# bpod_stepper_1_4_6.net
KiCad netlist of a schematic drawn in EAGLE
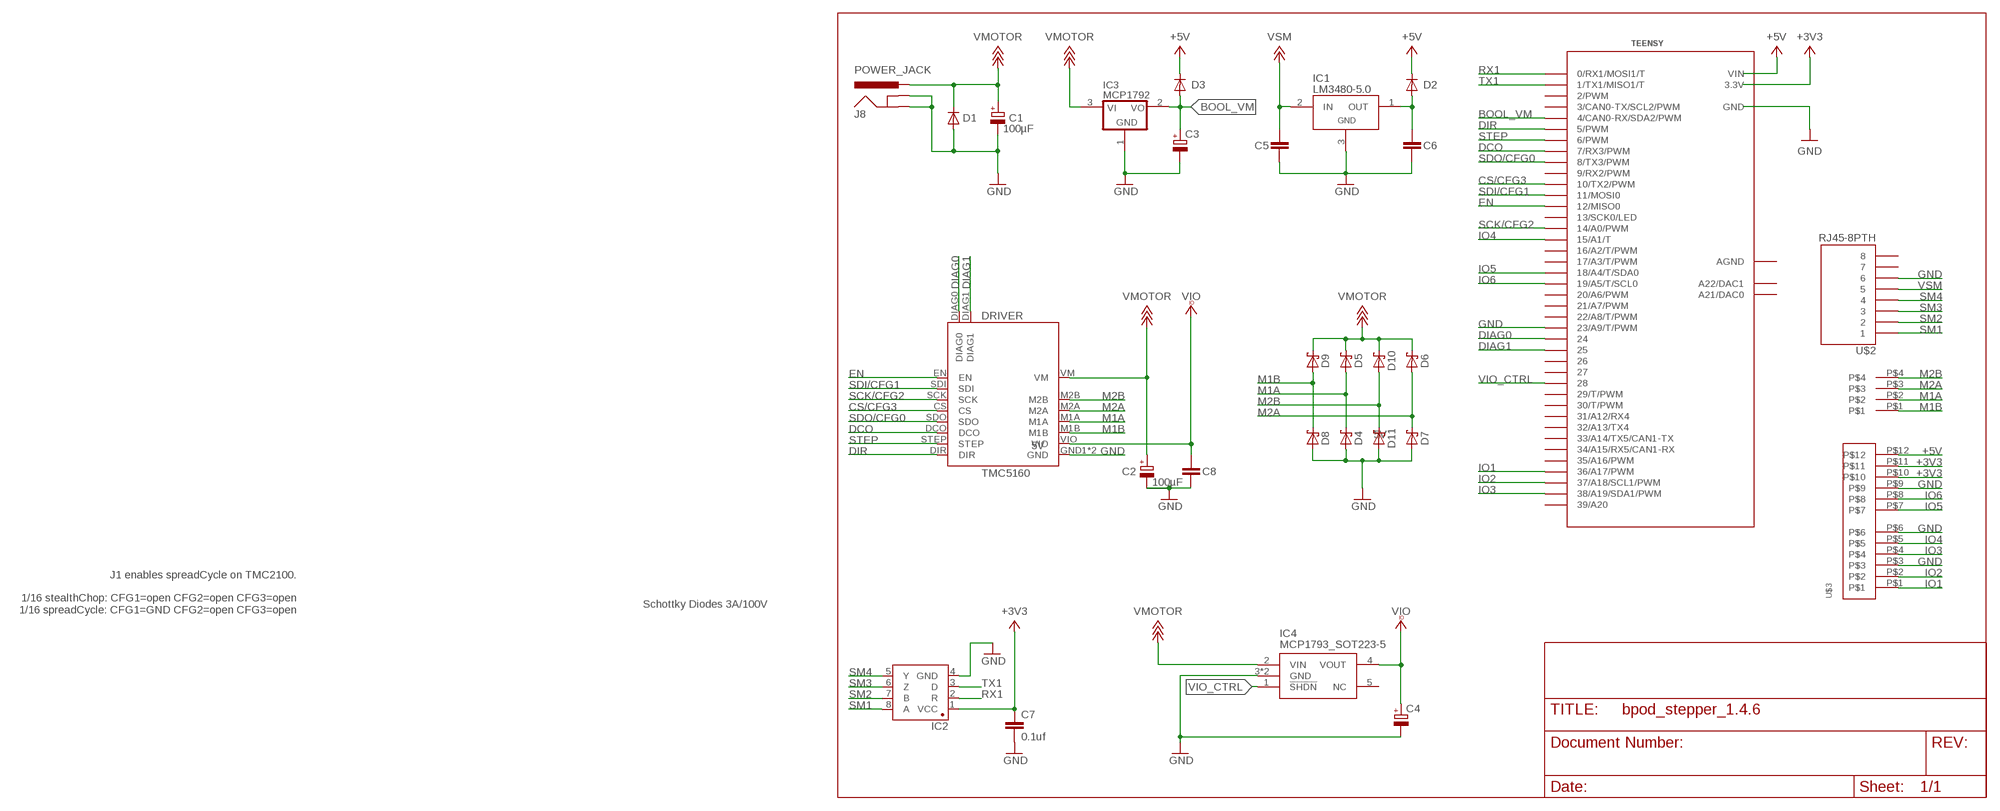
[diagram p0: schematic, sheet 1]

(export (version "E")
  (design (tool "Eeschema 10.0.6"))
  (components
    (comp (ref "C1")
      (value "100µF")
      (footprint "eagle-import:PANASONIC_G")
      (libsource (lib "eagle-import") (part "CPOL-EUG"))
    )
    (comp (ref "C2")
      (value "100µF")
      (footprint "eagle-import:PANASONIC_G")
      (libsource (lib "eagle-import") (part "CPOL-EUG"))
    )
    (comp (ref "C3")
      (value "CPOL-EUB")
      (footprint "eagle-import:PANASONIC_B")
      (libsource (lib "eagle-import") (part "CPOL-EUB"))
    )
    (comp (ref "C4")
      (value "CPOL-EUB")
      (footprint "eagle-import:PANASONIC_B")
      (libsource (lib "eagle-import") (part "CPOL-EUB"))
    )
    (comp (ref "C5")
      (value "0.1uf")
      (footprint "eagle-import:1206@1")
      (libsource (lib "eagle-import") (part "CAP1206"))
    )
    (comp (ref "C6")
      (value "0.1uf")
      (footprint "eagle-import:1206@1")
      (libsource (lib "eagle-import") (part "CAP1206"))
    )
    (comp (ref "C7")
      (value "0.1uf")
      (footprint "eagle-import:1206@1")
      (libsource (lib "eagle-import") (part "CAP1206"))
    )
    (comp (ref "C8")
      (value "100nf")
      (footprint "eagle-import:1206@1")
      (libsource (lib "eagle-import") (part "CAP1206"))
    )
    (comp (ref "D1")
      (value "DIODE-DO214AA")
      (footprint "eagle-import:DO214AA")
      (libsource (lib "eagle-import") (part "DIODE-DO214AA"))
    )
    (comp (ref "D2")
      (value "MBR0520LT")
      (footprint "eagle-import:SOD123")
      (libsource (lib "eagle-import") (part "MBR0520LT"))
    )
    (comp (ref "D3")
      (value "MBR0520LT")
      (footprint "eagle-import:SOD123")
      (libsource (lib "eagle-import") (part "MBR0520LT"))
    )
    (comp (ref "D4")
      (value "S310FA")
      (footprint "eagle-import:SOD123")
      (libsource (lib "eagle-import") (part "D_SCHOTTKY-SOD123"))
    )
    (comp (ref "D5")
      (value "S310FA")
      (footprint "eagle-import:SOD123")
      (libsource (lib "eagle-import") (part "D_SCHOTTKY-SOD123"))
    )
    (comp (ref "D6")
      (value "S310FA")
      (footprint "eagle-import:SOD123")
      (libsource (lib "eagle-import") (part "D_SCHOTTKY-SOD123"))
    )
    (comp (ref "D7")
      (value "S310FA")
      (footprint "eagle-import:SOD123")
      (libsource (lib "eagle-import") (part "D_SCHOTTKY-SOD123"))
    )
    (comp (ref "D8")
      (value "S310FA")
      (footprint "eagle-import:SOD123")
      (libsource (lib "eagle-import") (part "D_SCHOTTKY-SOD123"))
    )
    (comp (ref "D9")
      (value "S310FA")
      (footprint "eagle-import:SOD123")
      (libsource (lib "eagle-import") (part "D_SCHOTTKY-SOD123"))
    )
    (comp (ref "D10")
      (value "S310FA")
      (footprint "eagle-import:SOD123")
      (libsource (lib "eagle-import") (part "D_SCHOTTKY-SOD123"))
    )
    (comp (ref "D11")
      (value "S310FA")
      (footprint "eagle-import:SOD123")
      (libsource (lib "eagle-import") (part "D_SCHOTTKY-SOD123"))
    )
    (comp (ref "DRIVER")
      (value "TMC5160")
      (footprint "eagle-import:TMC5160")
      (libsource (lib "eagle-import") (part "TMC5160"))
    )
    (comp (ref "IC1")
      (value "LM3480-5.0")
      (footprint "eagle-import:SOT-23-3")
      (libsource (lib "eagle-import") (part "LM3480-5.0"))
    )
    (comp (ref "IC2")
      (value "SN65HVD31DR")
      (footprint "eagle-import:SO08")
      (libsource (lib "eagle-import") (part "SN65HVD31DR"))
    )
    (comp (ref "IC3")
      (value "MCP1792")
      (footprint "eagle-import:SOT23A_MICROCHIP_CB")
      (libsource (lib "eagle-import") (part "MCP170302E/CB-12"))
    )
    (comp (ref "IC4")
      (value "MCP1793_SOT223-5")
      (footprint "eagle-import:SOT223-5")
      (libsource (lib "eagle-import") (part "MCP1793_SOT223-5"))
    )
    (comp (ref "J8")
      (value "POWER_JACK")
      (footprint "eagle-import:POWER_JACK_PTH")
      (libsource (lib "eagle-import") (part "POWER_JACK"))
    )
    (comp (ref "TEENSY")
      (value "TEENSY_3.6_DIL")
      (footprint "eagle-import:TEENSY_3.6_DIL")
      (libsource (lib "eagle-import") (part "TEENSY_3.6_DIL"))
    )
    (comp (ref "U$2")
      (value "RJ45-8PTH")
      (footprint "eagle-import:RJ45-8")
      (libsource (lib "eagle-import") (part "RJ45-8PTH"))
    )
    (comp (ref "U$3")
      (value "12POS_MOLEX_SOCKET")
      (footprint "eagle-import:12POS_MOLEX_SOCKET")
      (libsource (lib "eagle-import") (part "12POS_MOLEX_SOCKET"))
    )
    (comp (ref "U$4")
      (value "MOLEX395221004")
      (footprint "eagle-import:MOLEX395221004")
      (libsource (lib "eagle-import") (part "MOLEX395221004"))
    )
  )
  (nets
    (net (code "1") (name "+3V3") (class "Default")
      (node (ref "C7") (pin "1") (pinfunction "1_1") (pintype "passive"))
      (node (ref "IC2") (pin "1") (pinfunction "VCC_1") (pintype "bidirectional"))
      (node (ref "TEENSY") (pin "3.3V") (pinfunction "3.3V_3.3V") (pintype "power_in"))
      (node (ref "TEENSY") (pin "3.3V3") (pinfunction "3.3V_3.3V3") (pintype "power_in"))
      (node (ref "U$3") (pin "P$10") (pinfunction "P$10_P$10") (pintype "bidirectional"))
      (node (ref "U$3") (pin "P$11") (pinfunction "P$11_P$11") (pintype "bidirectional"))
    )
    (net (code "2") (name "+5V") (class "Default")
      (node (ref "D2") (pin "C") (pinfunction "C_C") (pintype "passive"))
      (node (ref "D3") (pin "C") (pinfunction "C_C") (pintype "passive"))
      (node (ref "TEENSY") (pin "VIN") (pinfunction "VIN_VIN") (pintype "power_in"))
      (node (ref "U$3") (pin "P$12") (pinfunction "P$12_P$12") (pintype "bidirectional"))
    )
    (net (code "3") (name "+12V") (class "Default")
      (node (ref "C5") (pin "2") (pinfunction "2_2") (pintype "passive"))
      (node (ref "IC1") (pin "2") (pinfunction "IN_2") (pintype "power_in"))
      (node (ref "U$2") (pin "5") (pinfunction "5_5") (pintype "bidirectional"))
    )
    (net (code "4") (name "+18V") (class "Default")
      (node (ref "C1") (pin "+") (pinfunction "+_+") (pintype "passive"))
      (node (ref "C2") (pin "+") (pinfunction "+_+") (pintype "passive"))
      (node (ref "D1") (pin "C") (pinfunction "C_C") (pintype "passive"))
      (node (ref "D10") (pin "C") (pinfunction "C_C") (pintype "passive"))
      (node (ref "D5") (pin "C") (pinfunction "C_C") (pintype "passive"))
      (node (ref "D6") (pin "C") (pinfunction "C_C") (pintype "passive"))
      (node (ref "D9") (pin "C") (pinfunction "C_C") (pintype "passive"))
      (node (ref "DRIVER") (pin "VM") (pinfunction "VM_VM") (pintype "power_in"))
      (node (ref "IC3") (pin "3") (pinfunction "VI_3") (pintype "power_in"))
      (node (ref "IC4") (pin "2") (pinfunction "VIN_2") (pintype "bidirectional"))
      (node (ref "J8") (pin "PWR") (pinfunction "PWR_PWR") (pintype "bidirectional"))
    )
    (net (code "5") (name "/AGND") (class "Default")
      (node (ref "TEENSY") (pin "AGND") (pinfunction "AGND_AGND") (pintype "power_in"))
    )
    (net (code "6") (name "/CS{slash}CFG3") (class "Default")
      (node (ref "DRIVER") (pin "CS") (pinfunction "CS_CS") (pintype "passive"))
      (node (ref "TEENSY") (pin "10") (pinfunction "10/TX2/PWM_10") (pintype "bidirectional"))
    )
    (net (code "7") (name "/DCO") (class "Default")
      (node (ref "DRIVER") (pin "DCO") (pinfunction "DCO_DCO") (pintype "passive"))
      (node (ref "TEENSY") (pin "7") (pinfunction "7/RX3/PWM_7") (pintype "bidirectional"))
    )
    (net (code "8") (name "/DIAG0") (class "Default")
      (node (ref "DRIVER") (pin "DIAG0") (pinfunction "DIAG0_DIAG0") (pintype "passive"))
      (node (ref "TEENSY") (pin "24") (pinfunction "24_24") (pintype "bidirectional"))
    )
    (net (code "9") (name "/DIAG1") (class "Default")
      (node (ref "DRIVER") (pin "DIAG1") (pinfunction "DIAG1_DIAG1") (pintype "passive"))
      (node (ref "TEENSY") (pin "25") (pinfunction "25_25") (pintype "bidirectional"))
    )
    (net (code "10") (name "/DIR") (class "Default")
      (node (ref "DRIVER") (pin "DIR") (pinfunction "DIR_DIR") (pintype "input"))
      (node (ref "TEENSY") (pin "5") (pinfunction "5/PWM_5") (pintype "bidirectional"))
    )
    (net (code "11") (name "/EN") (class "Default")
      (node (ref "DRIVER") (pin "EN") (pinfunction "EN_EN") (pintype "passive"))
      (node (ref "TEENSY") (pin "12") (pinfunction "12/MISO0_12") (pintype "bidirectional"))
    )
    (net (code "12") (name "/IO1") (class "Default")
      (node (ref "TEENSY") (pin "36/A17") (pinfunction "36/A17/PWM_36/A17") (pintype "bidirectional"))
      (node (ref "U$3") (pin "P$1") (pinfunction "P$1_P$1") (pintype "bidirectional"))
    )
    (net (code "13") (name "/IO2") (class "Default")
      (node (ref "TEENSY") (pin "37/A18") (pinfunction "37/A18/SCL1/PWM_37/A18") (pintype "bidirectional"))
      (node (ref "U$3") (pin "P$2") (pinfunction "P$2_P$2") (pintype "bidirectional"))
    )
    (net (code "14") (name "/IO3") (class "Default")
      (node (ref "TEENSY") (pin "38/A19") (pinfunction "38/A19/SDA1/PWM_38/A19") (pintype "bidirectional"))
      (node (ref "U$3") (pin "P$4") (pinfunction "P$4_P$4") (pintype "bidirectional"))
    )
    (net (code "15") (name "/IO4") (class "Default")
      (node (ref "TEENSY") (pin "15/A1") (pinfunction "15/A1/T_15/A1") (pintype "bidirectional"))
      (node (ref "U$3") (pin "P$5") (pinfunction "P$5_P$5") (pintype "bidirectional"))
    )
    (net (code "16") (name "/IO5") (class "Default")
      (node (ref "TEENSY") (pin "18/A4") (pinfunction "18/A4/T/SDA0_18/A4") (pintype "bidirectional"))
      (node (ref "U$3") (pin "P$7") (pinfunction "P$7_P$7") (pintype "bidirectional"))
    )
    (net (code "17") (name "/IO6") (class "Default")
      (node (ref "TEENSY") (pin "19/A5") (pinfunction "19/A5/T/SCL0_19/A5") (pintype "bidirectional"))
      (node (ref "U$3") (pin "P$8") (pinfunction "P$8_P$8") (pintype "bidirectional"))
    )
    (net (code "18") (name "/M1A") (class "Default")
      (node (ref "D4") (pin "C") (pinfunction "C_C") (pintype "passive"))
      (node (ref "D5") (pin "A") (pinfunction "A_A") (pintype "passive"))
      (node (ref "DRIVER") (pin "M1A") (pinfunction "M1A_M1A") (pintype "output"))
      (node (ref "U$4") (pin "P$2") (pinfunction "P$2_P$2") (pintype "bidirectional"))
    )
    (net (code "19") (name "/M1B") (class "Default")
      (node (ref "D8") (pin "C") (pinfunction "C_C") (pintype "passive"))
      (node (ref "D9") (pin "A") (pinfunction "A_A") (pintype "passive"))
      (node (ref "DRIVER") (pin "M1B") (pinfunction "M1B_M1B") (pintype "output"))
      (node (ref "U$4") (pin "P$1") (pinfunction "P$1_P$1") (pintype "bidirectional"))
    )
    (net (code "20") (name "/M2A") (class "Default")
      (node (ref "D6") (pin "A") (pinfunction "A_A") (pintype "passive"))
      (node (ref "D7") (pin "C") (pinfunction "C_C") (pintype "passive"))
      (node (ref "DRIVER") (pin "M2A") (pinfunction "M2A_M2A") (pintype "output"))
      (node (ref "U$4") (pin "P$3") (pinfunction "P$3_P$3") (pintype "bidirectional"))
    )
    (net (code "21") (name "/M2B") (class "Default")
      (node (ref "D10") (pin "A") (pinfunction "A_A") (pintype "passive"))
      (node (ref "D11") (pin "C") (pinfunction "C_C") (pintype "passive"))
      (node (ref "DRIVER") (pin "M2B") (pinfunction "M2B_M2B") (pintype "output"))
      (node (ref "U$4") (pin "P$4") (pinfunction "P$4_P$4") (pintype "bidirectional"))
    )
    (net (code "22") (name "/RX1") (class "Default")
      (node (ref "IC2") (pin "2") (pinfunction "R_2") (pintype "bidirectional"))
      (node (ref "TEENSY") (pin "0") (pinfunction "0/RX1/MOSI1/T_0") (pintype "bidirectional"))
    )
    (net (code "23") (name "/SCK{slash}CFG2") (class "Default")
      (node (ref "DRIVER") (pin "SCK") (pinfunction "SCK_SCK") (pintype "passive"))
      (node (ref "TEENSY") (pin "14/A0") (pinfunction "14/A0/PWM_14/A0") (pintype "bidirectional"))
    )
    (net (code "24") (name "/SDI{slash}CFG1") (class "Default")
      (node (ref "DRIVER") (pin "SDI") (pinfunction "SDI_SDI") (pintype "passive"))
      (node (ref "TEENSY") (pin "11") (pinfunction "11/MOSI0_11") (pintype "bidirectional"))
    )
    (net (code "25") (name "/SDO{slash}CFG0") (class "Default")
      (node (ref "DRIVER") (pin "SDO") (pinfunction "SDO_SDO") (pintype "passive"))
      (node (ref "TEENSY") (pin "8") (pinfunction "8/TX3/PWM_8") (pintype "bidirectional"))
    )
    (net (code "26") (name "/SM1") (class "Default")
      (node (ref "IC2") (pin "8") (pinfunction "A_8") (pintype "bidirectional"))
      (node (ref "U$2") (pin "1") (pinfunction "1_1") (pintype "bidirectional"))
    )
    (net (code "27") (name "/SM2") (class "Default")
      (node (ref "IC2") (pin "7") (pinfunction "B_7") (pintype "bidirectional"))
      (node (ref "U$2") (pin "2") (pinfunction "2_2") (pintype "bidirectional"))
    )
    (net (code "28") (name "/SM3") (class "Default")
      (node (ref "IC2") (pin "6") (pinfunction "Z_6") (pintype "bidirectional"))
      (node (ref "U$2") (pin "3") (pinfunction "3_3") (pintype "bidirectional"))
    )
    (net (code "29") (name "/SM4") (class "Default")
      (node (ref "IC2") (pin "5") (pinfunction "Y_5") (pintype "bidirectional"))
      (node (ref "U$2") (pin "4") (pinfunction "4_4") (pintype "bidirectional"))
    )
    (net (code "30") (name "/STEP") (class "Default")
      (node (ref "DRIVER") (pin "STEP") (pinfunction "STEP_STEP") (pintype "input"))
      (node (ref "TEENSY") (pin "6") (pinfunction "6/PWM_6") (pintype "bidirectional"))
    )
    (net (code "31") (name "/TX1") (class "Default")
      (node (ref "IC2") (pin "3") (pinfunction "D_3") (pintype "bidirectional"))
      (node (ref "TEENSY") (pin "1") (pinfunction "1/TX1/MISO1/T_1") (pintype "bidirectional"))
    )
    (net (code "32") (name "BOOL_VM") (class "Default")
      (node (ref "C3") (pin "+") (pinfunction "+_+") (pintype "passive"))
      (node (ref "D3") (pin "A") (pinfunction "A_A") (pintype "passive"))
      (node (ref "IC3") (pin "2") (pinfunction "VO_2") (pintype "passive"))
      (node (ref "TEENSY") (pin "4") (pinfunction "4/CAN0-RX/SDA2/PWM_4") (pintype "bidirectional"))
    )
    (net (code "33") (name "GND") (class "Default")
      (node (ref "C1") (pin "-") (pinfunction "-_-") (pintype "passive"))
      (node (ref "C2") (pin "-") (pinfunction "-_-") (pintype "passive"))
      (node (ref "C3") (pin "-") (pinfunction "-_-") (pintype "passive"))
      (node (ref "C4") (pin "-") (pinfunction "-_-") (pintype "passive"))
      (node (ref "C5") (pin "1") (pinfunction "1_1") (pintype "passive"))
      (node (ref "C6") (pin "1") (pinfunction "1_1") (pintype "passive"))
      (node (ref "C7") (pin "2") (pinfunction "2_2") (pintype "passive"))
      (node (ref "C8") (pin "2") (pinfunction "2_2") (pintype "passive"))
      (node (ref "D1") (pin "A") (pinfunction "A_A") (pintype "passive"))
      (node (ref "D11") (pin "A") (pinfunction "A_A") (pintype "passive"))
      (node (ref "D4") (pin "A") (pinfunction "A_A") (pintype "passive"))
      (node (ref "D7") (pin "A") (pinfunction "A_A") (pintype "passive"))
      (node (ref "D8") (pin "A") (pinfunction "A_A") (pintype "passive"))
      (node (ref "DRIVER") (pin "GND1") (pinfunction "GND_GND1") (pintype "power_in"))
      (node (ref "DRIVER") (pin "GND2") (pinfunction "GND_GND2") (pintype "power_in"))
      (node (ref "IC1") (pin "3") (pinfunction "GND_3") (pintype "power_in"))
      (node (ref "IC2") (pin "4") (pinfunction "GND_4") (pintype "bidirectional"))
      (node (ref "IC3") (pin "1") (pinfunction "GND_1") (pintype "power_in"))
      (node (ref "IC4") (pin "3") (pinfunction "GND_3") (pintype "bidirectional"))
      (node (ref "IC4") (pin "6") (pinfunction "GND_6") (pintype "bidirectional"))
      (node (ref "J8") (pin "GND") (pinfunction "GND_GND") (pintype "bidirectional"))
      (node (ref "J8") (pin "GNDBREAK") (pinfunction "GNDBREAK_GNDBREAK") (pintype "bidirectional"))
      (node (ref "TEENSY") (pin "23/A9") (pinfunction "23/A9/T/PWM_23/A9") (pintype "bidirectional"))
      (node (ref "TEENSY") (pin "GND") (pinfunction "GND_GND") (pintype "power_in"))
      (node (ref "TEENSY") (pin "GND1") (pinfunction "GND_GND1") (pintype "power_in"))
      (node (ref "U$2") (pin "6") (pinfunction "6_6") (pintype "bidirectional"))
      (node (ref "U$3") (pin "P$3") (pinfunction "P$3_P$3") (pintype "bidirectional"))
      (node (ref "U$3") (pin "P$6") (pinfunction "P$6_P$6") (pintype "bidirectional"))
      (node (ref "U$3") (pin "P$9") (pinfunction "P$9_P$9") (pintype "bidirectional"))
    )
    (net (code "34") (name "Net-(IC1-OUT)") (class "Default")
      (node (ref "C6") (pin "2") (pinfunction "2_2") (pintype "passive"))
      (node (ref "D2") (pin "A") (pinfunction "A_A") (pintype "passive"))
      (node (ref "IC1") (pin "1") (pinfunction "OUT_1") (pintype "power_in"))
    )
    (net (code "35") (name "VCCIO") (class "Default")
      (node (ref "C4") (pin "+") (pinfunction "+_+") (pintype "passive"))
      (node (ref "C8") (pin "1") (pinfunction "1_1") (pintype "passive"))
      (node (ref "DRIVER") (pin "VIO") (pinfunction "VIO_VIO") (pintype "power_in"))
      (node (ref "IC4") (pin "4") (pinfunction "VOUT_4") (pintype "bidirectional"))
    )
    (net (code "36") (name "VIO_CTRL") (class "Default")
      (node (ref "IC4") (pin "1") (pinfunction "~{SHDN}_1") (pintype "bidirectional"))
      (node (ref "TEENSY") (pin "28") (pinfunction "28_28") (pintype "bidirectional"))
    )
    (net (code "37") (name "unconnected-(IC4-NC-Pad5)") (class "Default")
      (node (ref "IC4") (pin "5") (pinfunction "NC_5") (pintype "bidirectional"))
    )
    (net (code "38") (name "unconnected-(TEENSY-2{slash}PWM-Pad2)") (class "Default")
      (node (ref "TEENSY") (pin "2") (pinfunction "2/PWM_2") (pintype "bidirectional"))
    )
    (net (code "39") (name "unconnected-(TEENSY-3{slash}CAN0-TX{slash}SCL2{slash}PWM-Pad3)") (class "Default")
      (node (ref "TEENSY") (pin "3") (pinfunction "3/CAN0-TX/SCL2/PWM_3") (pintype "bidirectional"))
    )
    (net (code "40") (name "unconnected-(TEENSY-9{slash}RX2{slash}PWM-Pad9)") (class "Default")
      (node (ref "TEENSY") (pin "9") (pinfunction "9/RX2/PWM_9") (pintype "bidirectional"))
    )
    (net (code "41") (name "unconnected-(TEENSY-13{slash}SCK0{slash}LED-Pad13)") (class "Default")
      (node (ref "TEENSY") (pin "13") (pinfunction "13/SCK0/LED_13") (pintype "bidirectional"))
    )
    (net (code "42") (name "unconnected-(TEENSY-16{slash}A2{slash}T{slash}PWM-Pad16{slash}A2)") (class "Default")
      (node (ref "TEENSY") (pin "16/A2") (pinfunction "16/A2/T/PWM_16/A2") (pintype "bidirectional"))
    )
    (net (code "43") (name "unconnected-(TEENSY-17{slash}A3{slash}T{slash}PWM-Pad17{slash}A3)") (class "Default")
      (node (ref "TEENSY") (pin "17/A3") (pinfunction "17/A3/T/PWM_17/A3") (pintype "bidirectional"))
    )
    (net (code "44") (name "unconnected-(TEENSY-20{slash}A6{slash}PWM-Pad20{slash}A6)") (class "Default")
      (node (ref "TEENSY") (pin "20/A6") (pinfunction "20/A6/PWM_20/A6") (pintype "bidirectional"))
    )
    (net (code "45") (name "unconnected-(TEENSY-21{slash}A7{slash}PWM-Pad21{slash}A7)") (class "Default")
      (node (ref "TEENSY") (pin "21/A7") (pinfunction "21/A7/PWM_21/A7") (pintype "bidirectional"))
    )
    (net (code "46") (name "unconnected-(TEENSY-22{slash}A8{slash}T{slash}PWM-Pad22{slash}A8)") (class "Default")
      (node (ref "TEENSY") (pin "22/A8") (pinfunction "22/A8/T/PWM_22/A8") (pintype "bidirectional"))
    )
    (net (code "47") (name "unconnected-(TEENSY-29{slash}T{slash}PWM-Pad29)") (class "Default")
      (node (ref "TEENSY") (pin "29") (pinfunction "29/T/PWM_29") (pintype "bidirectional"))
    )
    (net (code "48") (name "unconnected-(TEENSY-30{slash}T{slash}PWM-Pad30)") (class "Default")
      (node (ref "TEENSY") (pin "30") (pinfunction "30/T/PWM_30") (pintype "bidirectional"))
    )
    (net (code "49") (name "unconnected-(TEENSY-31{slash}A12{slash}RX4-Pad31{slash}A12)") (class "Default")
      (node (ref "TEENSY") (pin "31/A12") (pinfunction "31/A12/RX4_31/A12") (pintype "bidirectional"))
    )
    (net (code "50") (name "unconnected-(TEENSY-32{slash}A13{slash}TX4-Pad32{slash}A13)") (class "Default")
      (node (ref "TEENSY") (pin "32/A13") (pinfunction "32/A13/TX4_32/A13") (pintype "bidirectional"))
    )
    (net (code "51") (name "unconnected-(TEENSY-33{slash}A14{slash}TX5{slash}CAN1-TX-Pad33{slash}A14)") (class "Default")
      (node (ref "TEENSY") (pin "33/A14") (pinfunction "33/A14/TX5/CAN1-TX_33/A14") (pintype "bidirectional"))
    )
    (net (code "52") (name "unconnected-(TEENSY-34{slash}A15{slash}RX5{slash}CAN1-RX-Pad34{slash}A15)") (class "Default")
      (node (ref "TEENSY") (pin "34/A15") (pinfunction "34/A15/RX5/CAN1-RX_34/A15") (pintype "bidirectional"))
    )
    (net (code "53") (name "unconnected-(TEENSY-35{slash}A16{slash}PWM-Pad35{slash}A16)") (class "Default")
      (node (ref "TEENSY") (pin "35/A16") (pinfunction "35/A16/PWM_35/A16") (pintype "bidirectional"))
    )
    (net (code "54") (name "unconnected-(TEENSY-A21{slash}DAC0-PadA21)") (class "Default")
      (node (ref "TEENSY") (pin "A21") (pinfunction "A21/DAC0_A21") (pintype "bidirectional"))
    )
    (net (code "55") (name "unconnected-(TEENSY-A22{slash}DAC1-PadA22)") (class "Default")
      (node (ref "TEENSY") (pin "A22") (pinfunction "A22/DAC1_A22") (pintype "bidirectional"))
    )
    (net (code "56") (name "unconnected-(TEENSY-Pad26)") (class "Default")
      (node (ref "TEENSY") (pin "26") (pinfunction "26_26") (pintype "bidirectional"))
    )
    (net (code "57") (name "unconnected-(TEENSY-Pad27)") (class "Default")
      (node (ref "TEENSY") (pin "27") (pinfunction "27_27") (pintype "bidirectional"))
    )
    (net (code "58") (name "unconnected-(TEENSY-Pad39{slash}A20)") (class "Default")
      (node (ref "TEENSY") (pin "39/A20") (pinfunction "39/A20_39/A20") (pintype "bidirectional"))
    )
    (net (code "59") (name "unconnected-(U$2-Pad7)") (class "Default")
      (node (ref "U$2") (pin "7") (pinfunction "7_7") (pintype "bidirectional"))
    )
    (net (code "60") (name "unconnected-(U$2-Pad8)") (class "Default")
      (node (ref "U$2") (pin "8") (pinfunction "8_8") (pintype "bidirectional"))
    )
  )
)
